# 19_PWR_VRS.net
KiCad netlist of a schematic drawn in Altium Designer
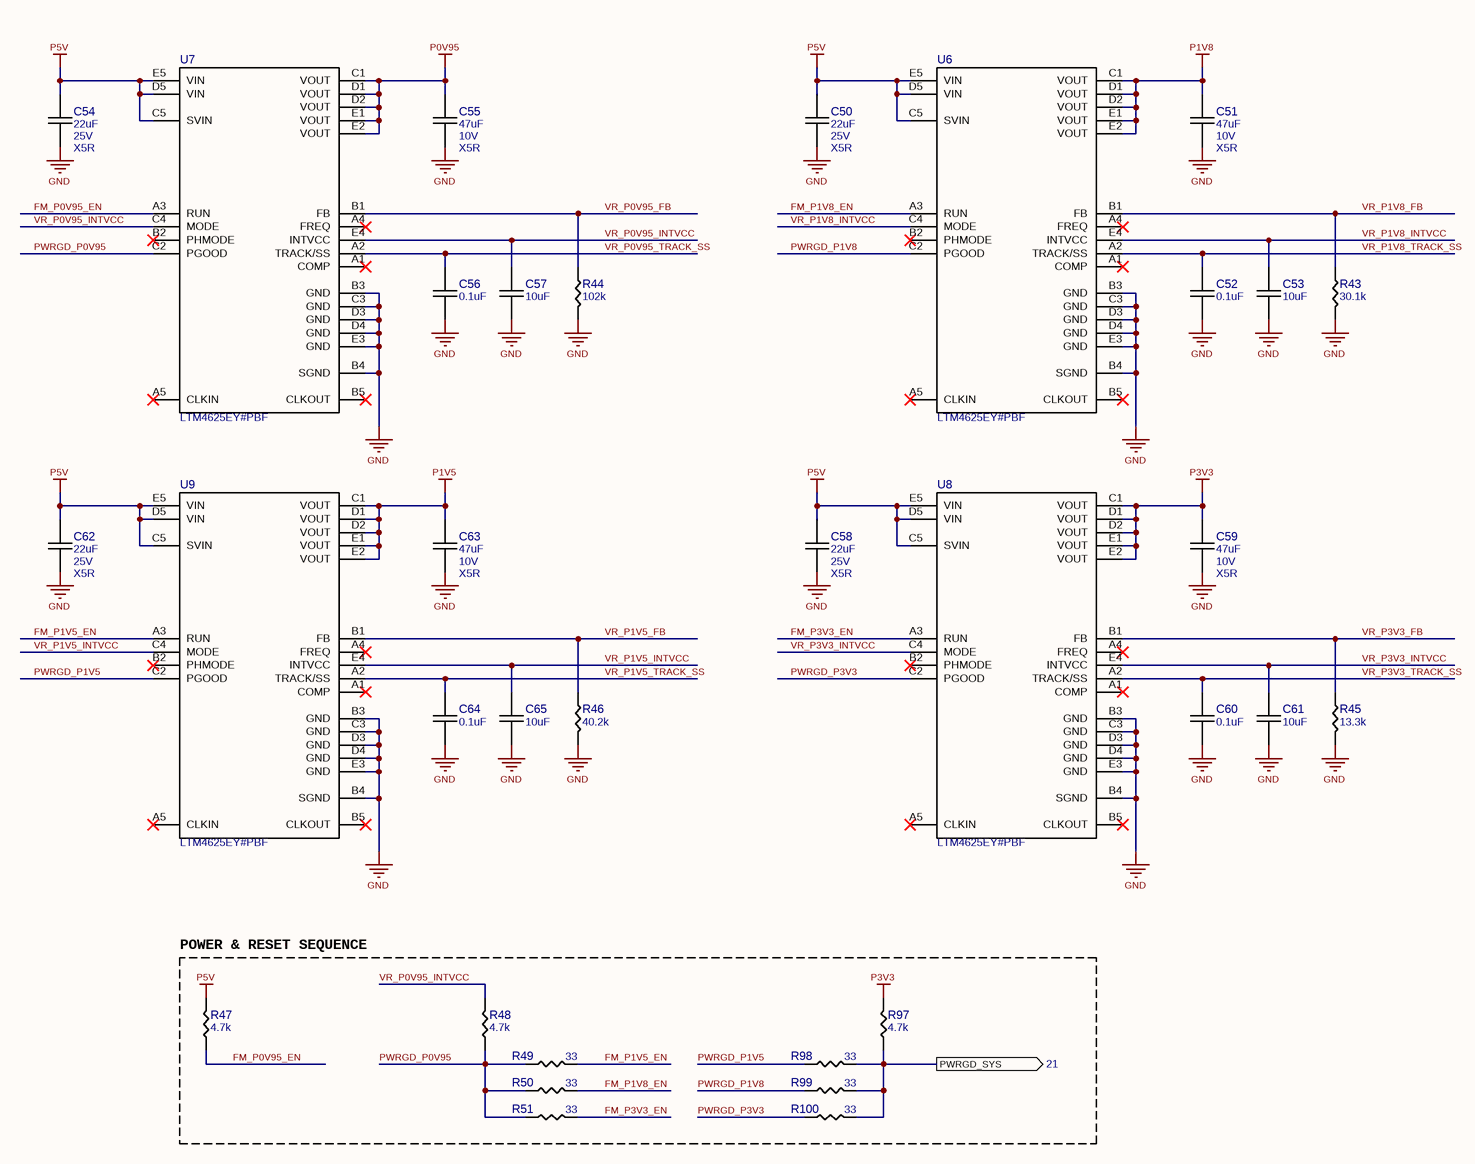
[diagram p0: 19_PWR_VRS.SchDoc]

(export (version "E")
  (design (tool "Eeschema 10.0.6"))
  (components
    (comp (ref "C50")
      (value "22uF")
      (footprint "CAPC2012X14N")
      (description "CAP CER 22UF 25V X5R 0805")
      (fields
        (field (name "PART NUMBER") "GRM21BR61E226ME44L")
        (field (name "VOLTAGE") "25V")
        (field (name "TEMPC") "X5R")
      )
      (libsource (lib "Database") (part "Capacitor"))
    )
    (comp (ref "C51")
      (value "47uF")
      (footprint "CAPC2012X14N")
      (description "CAP CER 47UF 10V X5R 0805")
      (fields
        (field (name "PART NUMBER") "GRM21BR61A476ME15L")
        (field (name "VOLTAGE") "10V")
        (field (name "TEMPC") "X5R")
      )
      (libsource (lib "Database") (part "Capacitor"))
    )
    (comp (ref "C52")
      (value "0.1uF")
      (footprint "CAPC1005X06N")
      (description "CAP CER 0.1UF 25V X7R 0402")
      (fields (field (name "PART NUMBER") "GRM155R71E104KE14J") (field (name "VOLTAGE") "25V"))
      (libsource (lib "Database") (part "Capacitor"))
    )
    (comp (ref "C53")
      (value "10uF")
      (footprint "CAPC1005X06N")
      (description "CAP CER 10UF 6.3V X5R 0402")
      (fields (field (name "PART NUMBER") "GRM155R60J106ME47D") (field (name "VOLTAGE") "6.3V"))
      (libsource (lib "Database") (part "Capacitor"))
    )
    (comp (ref "C54")
      (value "22uF")
      (footprint "CAPC2012X14N")
      (description "CAP CER 22UF 25V X5R 0805")
      (fields
        (field (name "PART NUMBER") "GRM21BR61E226ME44L")
        (field (name "VOLTAGE") "25V")
        (field (name "TEMPC") "X5R")
      )
      (libsource (lib "Database") (part "Capacitor"))
    )
    (comp (ref "C55")
      (value "47uF")
      (footprint "CAPC2012X14N")
      (description "CAP CER 47UF 10V X5R 0805")
      (fields
        (field (name "PART NUMBER") "GRM21BR61A476ME15L")
        (field (name "VOLTAGE") "10V")
        (field (name "TEMPC") "X5R")
      )
      (libsource (lib "Database") (part "Capacitor"))
    )
    (comp (ref "C56")
      (value "0.1uF")
      (footprint "CAPC1005X06N")
      (description "CAP CER 0.1UF 25V X7R 0402")
      (fields (field (name "PART NUMBER") "GRM155R71E104KE14J") (field (name "VOLTAGE") "25V"))
      (libsource (lib "Database") (part "Capacitor"))
    )
    (comp (ref "C57")
      (value "10uF")
      (footprint "CAPC1005X06N")
      (description "CAP CER 10UF 6.3V X5R 0402")
      (fields (field (name "PART NUMBER") "GRM155R60J106ME47D") (field (name "VOLTAGE") "6.3V"))
      (libsource (lib "Database") (part "Capacitor"))
    )
    (comp (ref "C58")
      (value "22uF")
      (footprint "CAPC2012X14N")
      (description "CAP CER 22UF 25V X5R 0805")
      (fields
        (field (name "PART NUMBER") "GRM21BR61E226ME44L")
        (field (name "VOLTAGE") "25V")
        (field (name "TEMPC") "X5R")
      )
      (libsource (lib "Database") (part "Capacitor"))
    )
    (comp (ref "C59")
      (value "47uF")
      (footprint "CAPC2012X14N")
      (description "CAP CER 47UF 10V X5R 0805")
      (fields
        (field (name "PART NUMBER") "GRM21BR61A476ME15L")
        (field (name "VOLTAGE") "10V")
        (field (name "TEMPC") "X5R")
      )
      (libsource (lib "Database") (part "Capacitor"))
    )
    (comp (ref "C60")
      (value "0.1uF")
      (footprint "CAPC1005X06N")
      (description "CAP CER 0.1UF 25V X7R 0402")
      (fields (field (name "PART NUMBER") "GRM155R71E104KE14J") (field (name "VOLTAGE") "25V"))
      (libsource (lib "Database") (part "Capacitor"))
    )
    (comp (ref "C61")
      (value "10uF")
      (footprint "CAPC1005X06N")
      (description "CAP CER 10UF 6.3V X5R 0402")
      (fields (field (name "PART NUMBER") "GRM155R60J106ME47D") (field (name "VOLTAGE") "6.3V"))
      (libsource (lib "Database") (part "Capacitor"))
    )
    (comp (ref "C62")
      (value "22uF")
      (footprint "CAPC2012X14N")
      (description "CAP CER 22UF 25V X5R 0805")
      (fields
        (field (name "PART NUMBER") "GRM21BR61E226ME44L")
        (field (name "VOLTAGE") "25V")
        (field (name "TEMPC") "X5R")
      )
      (libsource (lib "Database") (part "Capacitor"))
    )
    (comp (ref "C63")
      (value "47uF")
      (footprint "CAPC2012X14N")
      (description "CAP CER 47UF 10V X5R 0805")
      (fields
        (field (name "PART NUMBER") "GRM21BR61A476ME15L")
        (field (name "VOLTAGE") "10V")
        (field (name "TEMPC") "X5R")
      )
      (libsource (lib "Database") (part "Capacitor"))
    )
    (comp (ref "C64")
      (value "0.1uF")
      (footprint "CAPC1005X06N")
      (description "CAP CER 0.1UF 25V X7R 0402")
      (fields (field (name "PART NUMBER") "GRM155R71E104KE14J") (field (name "VOLTAGE") "25V"))
      (libsource (lib "Database") (part "Capacitor"))
    )
    (comp (ref "C65")
      (value "10uF")
      (footprint "CAPC1005X06N")
      (description "CAP CER 10UF 6.3V X5R 0402")
      (fields (field (name "PART NUMBER") "GRM155R60J106ME47D") (field (name "VOLTAGE") "6.3V"))
      (libsource (lib "Database") (part "Capacitor"))
    )
    (comp (ref "R43")
      (value "30.1k")
      (footprint "RESC1005X03N")
      (description "RES 30.1K OHM 1% 1/16W 0402")
      (fields (field (name "PART NUMBER") "RC0402FR-0730K1L"))
      (libsource (lib "Database") (part "Resistor_ENG"))
    )
    (comp (ref "R44")
      (value "102k")
      (footprint "RESC1005X03N")
      (description "RES SMD 102K OHM 1% 1/16W 0402")
      (fields (field (name "PART NUMBER") "RC0402FR-07102KL"))
      (libsource (lib "Database") (part "Resistor_ENG"))
    )
    (comp (ref "R45")
      (value "13.3k")
      (footprint "RESC1005X03N")
      (description "RES 13.3K OHM 1% 1/16W 0402")
      (fields (field (name "PART NUMBER") "RC0402FR-0713K3L"))
      (libsource (lib "Database") (part "Resistor_ENG"))
    )
    (comp (ref "R46")
      (value "40.2k")
      (footprint "RESC1005X03N")
      (description "RES 40.2K OHM 1% 1/16W 0402")
      (fields (field (name "PART NUMBER") "RC0402FR-0740K2L"))
      (libsource (lib "Database") (part "Resistor_ENG"))
    )
    (comp (ref "R47")
      (value "4.7k")
      (footprint "RESC1005X03N")
      (description "RES SMD 4.7K OHM 1% 1/16W 0402")
      (fields (field (name "PART NUMBER") "RC0402FR-074K7L"))
      (libsource (lib "Database") (part "Resistor_ENG"))
    )
    (comp (ref "R48")
      (value "4.7k")
      (footprint "RESC1005X03N")
      (description "RES SMD 4.7K OHM 1% 1/16W 0402")
      (fields (field (name "PART NUMBER") "RC0402FR-074K7L"))
      (libsource (lib "Database") (part "Resistor_ENG"))
    )
    (comp (ref "R49")
      (value "33")
      (footprint "RESC1005X03N")
      (description "RES SMD 33 OHM 1% 1/16W 0402")
      (fields (field (name "PART NUMBER") "RC0402FR-0733RL"))
      (libsource (lib "Database") (part "Resistor_ENG"))
    )
    (comp (ref "R50")
      (value "33")
      (footprint "RESC1005X03N")
      (description "RES SMD 33 OHM 1% 1/16W 0402")
      (fields (field (name "PART NUMBER") "RC0402FR-0733RL"))
      (libsource (lib "Database") (part "Resistor_ENG"))
    )
    (comp (ref "R51")
      (value "33")
      (footprint "RESC1005X03N")
      (description "RES SMD 33 OHM 1% 1/16W 0402")
      (fields (field (name "PART NUMBER") "RC0402FR-0733RL"))
      (libsource (lib "Database") (part "Resistor_ENG"))
    )
    (comp (ref "R97")
      (value "4.7k")
      (footprint "RESC1005X03N")
      (description "RES SMD 4.7K OHM 1% 1/16W 0402")
      (fields (field (name "PART NUMBER") "RC0402FR-074K7L"))
      (libsource (lib "Database") (part "Resistor_ENG"))
    )
    (comp (ref "R98")
      (value "33")
      (footprint "RESC1005X03N")
      (description "RES SMD 33 OHM 1% 1/16W 0402")
      (fields (field (name "PART NUMBER") "RC0402FR-0733RL"))
      (libsource (lib "Database") (part "Resistor_ENG"))
    )
    (comp (ref "R99")
      (value "33")
      (footprint "RESC1005X03N")
      (description "RES SMD 33 OHM 1% 1/16W 0402")
      (fields (field (name "PART NUMBER") "RC0402FR-0733RL"))
      (libsource (lib "Database") (part "Resistor_ENG"))
    )
    (comp (ref "R100")
      (value "33")
      (footprint "RESC1005X03N")
      (description "RES SMD 33 OHM 1% 1/16W 0402")
      (fields (field (name "PART NUMBER") "RC0402FR-0733RL"))
      (libsource (lib "Database") (part "Resistor_ENG"))
    )
    (comp (ref "U6")
      (value "LTM4625EY#PBF")
      (footprint "BGA25C127P5X5_625X625X521")
      (description "DC DC CONVERTER 0.6-5.5V")
      (libsource (lib "Database") (part "LTM4625"))
    )
    (comp (ref "U7")
      (value "LTM4625EY#PBF")
      (footprint "BGA25C127P5X5_625X625X521")
      (description "DC DC CONVERTER 0.6-5.5V")
      (libsource (lib "Database") (part "LTM4625"))
    )
    (comp (ref "U8")
      (value "LTM4625EY#PBF")
      (footprint "BGA25C127P5X5_625X625X521")
      (description "DC DC CONVERTER 0.6-5.5V")
      (libsource (lib "Database") (part "LTM4625"))
    )
    (comp (ref "U9")
      (value "LTM4625EY#PBF")
      (footprint "BGA25C127P5X5_625X625X521")
      (description "DC DC CONVERTER 0.6-5.5V")
      (libsource (lib "Database") (part "LTM4625"))
    )
  )
  (nets
    (net (code "1") (name "/FM_P0V95_EN") (class "Default")
      (node (ref "R47") (pin "1") (pinfunction "1_1") (pintype "passive"))
      (node (ref "U7") (pin "A3") (pinfunction "RUN_A3") (pintype "passive"))
    )
    (net (code "2") (name "/FM_P1V5_EN") (class "Default")
      (node (ref "R49") (pin "2") (pinfunction "2_2") (pintype "passive"))
      (node (ref "U9") (pin "A3") (pinfunction "RUN_A3") (pintype "passive"))
    )
    (net (code "3") (name "/FM_P1V8_EN") (class "Default")
      (node (ref "R50") (pin "2") (pinfunction "2_2") (pintype "passive"))
      (node (ref "U6") (pin "A3") (pinfunction "RUN_A3") (pintype "passive"))
    )
    (net (code "4") (name "/FM_P3V3_EN") (class "Default")
      (node (ref "R51") (pin "2") (pinfunction "2_2") (pintype "passive"))
      (node (ref "U8") (pin "A3") (pinfunction "RUN_A3") (pintype "passive"))
    )
    (net (code "5") (name "/PWRGD_P0V95") (class "Default")
      (node (ref "R48") (pin "1") (pinfunction "1_1") (pintype "passive"))
      (node (ref "R49") (pin "1") (pinfunction "1_1") (pintype "passive"))
      (node (ref "R50") (pin "1") (pinfunction "1_1") (pintype "passive"))
      (node (ref "R51") (pin "1") (pinfunction "1_1") (pintype "passive"))
      (node (ref "U7") (pin "C2") (pinfunction "PGOOD_C2") (pintype "passive"))
    )
    (net (code "6") (name "/PWRGD_P1V5") (class "Default")
      (node (ref "R98") (pin "1") (pinfunction "1_1") (pintype "passive"))
      (node (ref "U9") (pin "C2") (pinfunction "PGOOD_C2") (pintype "passive"))
    )
    (net (code "7") (name "/PWRGD_P1V8") (class "Default")
      (node (ref "R99") (pin "1") (pinfunction "1_1") (pintype "passive"))
      (node (ref "U6") (pin "C2") (pinfunction "PGOOD_C2") (pintype "passive"))
    )
    (net (code "8") (name "/PWRGD_P3V3") (class "Default")
      (node (ref "R100") (pin "1") (pinfunction "1_1") (pintype "passive"))
      (node (ref "U8") (pin "C2") (pinfunction "PGOOD_C2") (pintype "passive"))
    )
    (net (code "9") (name "/PWRGD_SYS") (class "Default")
      (node (ref "R100") (pin "2") (pinfunction "2_2") (pintype "passive"))
      (node (ref "R97") (pin "1") (pinfunction "1_1") (pintype "passive"))
      (node (ref "R98") (pin "2") (pinfunction "2_2") (pintype "passive"))
      (node (ref "R99") (pin "2") (pinfunction "2_2") (pintype "passive"))
    )
    (net (code "10") (name "/VR_P0V95_FB") (class "Default")
      (node (ref "R44") (pin "1") (pinfunction "1_1") (pintype "passive"))
      (node (ref "U7") (pin "B1") (pinfunction "FB_B1") (pintype "passive"))
    )
    (net (code "11") (name "/VR_P0V95_INTVCC") (class "Default")
      (node (ref "C57") (pin "2") (pinfunction "2_2") (pintype "passive"))
      (node (ref "R48") (pin "2") (pinfunction "2_2") (pintype "passive"))
      (node (ref "U7") (pin "C4") (pinfunction "MODE_C4") (pintype "passive"))
      (node (ref "U7") (pin "E4") (pinfunction "INTVCC_E4") (pintype "passive"))
    )
    (net (code "12") (name "/VR_P0V95_TRACK_SS") (class "Default")
      (node (ref "C56") (pin "2") (pinfunction "2_2") (pintype "passive"))
      (node (ref "U7") (pin "A2") (pinfunction "TRACK/SS_A2") (pintype "passive"))
    )
    (net (code "13") (name "/VR_P1V5_FB") (class "Default")
      (node (ref "R46") (pin "1") (pinfunction "1_1") (pintype "passive"))
      (node (ref "U9") (pin "B1") (pinfunction "FB_B1") (pintype "passive"))
    )
    (net (code "14") (name "/VR_P1V5_INTVCC") (class "Default")
      (node (ref "C65") (pin "2") (pinfunction "2_2") (pintype "passive"))
      (node (ref "U9") (pin "C4") (pinfunction "MODE_C4") (pintype "passive"))
      (node (ref "U9") (pin "E4") (pinfunction "INTVCC_E4") (pintype "passive"))
    )
    (net (code "15") (name "/VR_P1V5_TRACK_SS") (class "Default")
      (node (ref "C64") (pin "2") (pinfunction "2_2") (pintype "passive"))
      (node (ref "U9") (pin "A2") (pinfunction "TRACK/SS_A2") (pintype "passive"))
    )
    (net (code "16") (name "/VR_P1V8_FB") (class "Default")
      (node (ref "R43") (pin "1") (pinfunction "1_1") (pintype "passive"))
      (node (ref "U6") (pin "B1") (pinfunction "FB_B1") (pintype "passive"))
    )
    (net (code "17") (name "/VR_P1V8_INTVCC") (class "Default")
      (node (ref "C53") (pin "2") (pinfunction "2_2") (pintype "passive"))
      (node (ref "U6") (pin "C4") (pinfunction "MODE_C4") (pintype "passive"))
      (node (ref "U6") (pin "E4") (pinfunction "INTVCC_E4") (pintype "passive"))
    )
    (net (code "18") (name "/VR_P1V8_TRACK_SS") (class "Default")
      (node (ref "C52") (pin "2") (pinfunction "2_2") (pintype "passive"))
      (node (ref "U6") (pin "A2") (pinfunction "TRACK/SS_A2") (pintype "passive"))
    )
    (net (code "19") (name "/VR_P3V3_FB") (class "Default")
      (node (ref "R45") (pin "1") (pinfunction "1_1") (pintype "passive"))
      (node (ref "U8") (pin "B1") (pinfunction "FB_B1") (pintype "passive"))
    )
    (net (code "20") (name "/VR_P3V3_INTVCC") (class "Default")
      (node (ref "C61") (pin "2") (pinfunction "2_2") (pintype "passive"))
      (node (ref "U8") (pin "C4") (pinfunction "MODE_C4") (pintype "passive"))
      (node (ref "U8") (pin "E4") (pinfunction "INTVCC_E4") (pintype "passive"))
    )
    (net (code "21") (name "/VR_P3V3_TRACK_SS") (class "Default")
      (node (ref "C60") (pin "2") (pinfunction "2_2") (pintype "passive"))
      (node (ref "U8") (pin "A2") (pinfunction "TRACK/SS_A2") (pintype "passive"))
    )
    (net (code "22") (name "GND") (class "Default")
      (node (ref "C50") (pin "1") (pinfunction "1_1") (pintype "passive"))
      (node (ref "C51") (pin "1") (pinfunction "1_1") (pintype "passive"))
      (node (ref "C52") (pin "1") (pinfunction "1_1") (pintype "passive"))
      (node (ref "C53") (pin "1") (pinfunction "1_1") (pintype "passive"))
      (node (ref "C54") (pin "1") (pinfunction "1_1") (pintype "passive"))
      (node (ref "C55") (pin "1") (pinfunction "1_1") (pintype "passive"))
      (node (ref "C56") (pin "1") (pinfunction "1_1") (pintype "passive"))
      (node (ref "C57") (pin "1") (pinfunction "1_1") (pintype "passive"))
      (node (ref "C58") (pin "1") (pinfunction "1_1") (pintype "passive"))
      (node (ref "C59") (pin "1") (pinfunction "1_1") (pintype "passive"))
      (node (ref "C60") (pin "1") (pinfunction "1_1") (pintype "passive"))
      (node (ref "C61") (pin "1") (pinfunction "1_1") (pintype "passive"))
      (node (ref "C62") (pin "1") (pinfunction "1_1") (pintype "passive"))
      (node (ref "C63") (pin "1") (pinfunction "1_1") (pintype "passive"))
      (node (ref "C64") (pin "1") (pinfunction "1_1") (pintype "passive"))
      (node (ref "C65") (pin "1") (pinfunction "1_1") (pintype "passive"))
      (node (ref "R43") (pin "2") (pinfunction "2_2") (pintype "passive"))
      (node (ref "R44") (pin "2") (pinfunction "2_2") (pintype "passive"))
      (node (ref "R45") (pin "2") (pinfunction "2_2") (pintype "passive"))
      (node (ref "R46") (pin "2") (pinfunction "2_2") (pintype "passive"))
      (node (ref "U6") (pin "B3") (pinfunction "GND_B3") (pintype "passive"))
      (node (ref "U6") (pin "B4") (pinfunction "SGND_B4") (pintype "passive"))
      (node (ref "U6") (pin "C3") (pinfunction "GND_C3") (pintype "passive"))
      (node (ref "U6") (pin "D3") (pinfunction "GND_D3") (pintype "passive"))
      (node (ref "U6") (pin "D4") (pinfunction "GND_D4") (pintype "passive"))
      (node (ref "U6") (pin "E3") (pinfunction "GND_E3") (pintype "passive"))
      (node (ref "U7") (pin "B3") (pinfunction "GND_B3") (pintype "passive"))
      (node (ref "U7") (pin "B4") (pinfunction "SGND_B4") (pintype "passive"))
      (node (ref "U7") (pin "C3") (pinfunction "GND_C3") (pintype "passive"))
      (node (ref "U7") (pin "D3") (pinfunction "GND_D3") (pintype "passive"))
      (node (ref "U7") (pin "D4") (pinfunction "GND_D4") (pintype "passive"))
      (node (ref "U7") (pin "E3") (pinfunction "GND_E3") (pintype "passive"))
      (node (ref "U8") (pin "B3") (pinfunction "GND_B3") (pintype "passive"))
      (node (ref "U8") (pin "B4") (pinfunction "SGND_B4") (pintype "passive"))
      (node (ref "U8") (pin "C3") (pinfunction "GND_C3") (pintype "passive"))
      (node (ref "U8") (pin "D3") (pinfunction "GND_D3") (pintype "passive"))
      (node (ref "U8") (pin "D4") (pinfunction "GND_D4") (pintype "passive"))
      (node (ref "U8") (pin "E3") (pinfunction "GND_E3") (pintype "passive"))
      (node (ref "U9") (pin "B3") (pinfunction "GND_B3") (pintype "passive"))
      (node (ref "U9") (pin "B4") (pinfunction "SGND_B4") (pintype "passive"))
      (node (ref "U9") (pin "C3") (pinfunction "GND_C3") (pintype "passive"))
      (node (ref "U9") (pin "D3") (pinfunction "GND_D3") (pintype "passive"))
      (node (ref "U9") (pin "D4") (pinfunction "GND_D4") (pintype "passive"))
      (node (ref "U9") (pin "E3") (pinfunction "GND_E3") (pintype "passive"))
    )
    (net (code "23") (name "P0V95") (class "Default")
      (node (ref "C55") (pin "2") (pinfunction "2_2") (pintype "passive"))
      (node (ref "U7") (pin "C1") (pinfunction "VOUT_C1") (pintype "passive"))
      (node (ref "U7") (pin "D1") (pinfunction "VOUT_D1") (pintype "passive"))
      (node (ref "U7") (pin "D2") (pinfunction "VOUT_D2") (pintype "passive"))
      (node (ref "U7") (pin "E1") (pinfunction "VOUT_E1") (pintype "passive"))
      (node (ref "U7") (pin "E2") (pinfunction "VOUT_E2") (pintype "passive"))
    )
    (net (code "24") (name "P1V5") (class "Default")
      (node (ref "C63") (pin "2") (pinfunction "2_2") (pintype "passive"))
      (node (ref "U9") (pin "C1") (pinfunction "VOUT_C1") (pintype "passive"))
      (node (ref "U9") (pin "D1") (pinfunction "VOUT_D1") (pintype "passive"))
      (node (ref "U9") (pin "D2") (pinfunction "VOUT_D2") (pintype "passive"))
      (node (ref "U9") (pin "E1") (pinfunction "VOUT_E1") (pintype "passive"))
      (node (ref "U9") (pin "E2") (pinfunction "VOUT_E2") (pintype "passive"))
    )
    (net (code "25") (name "P1V8") (class "Default")
      (node (ref "C51") (pin "2") (pinfunction "2_2") (pintype "passive"))
      (node (ref "U6") (pin "C1") (pinfunction "VOUT_C1") (pintype "passive"))
      (node (ref "U6") (pin "D1") (pinfunction "VOUT_D1") (pintype "passive"))
      (node (ref "U6") (pin "D2") (pinfunction "VOUT_D2") (pintype "passive"))
      (node (ref "U6") (pin "E1") (pinfunction "VOUT_E1") (pintype "passive"))
      (node (ref "U6") (pin "E2") (pinfunction "VOUT_E2") (pintype "passive"))
    )
    (net (code "26") (name "P3V3") (class "Default")
      (node (ref "C59") (pin "2") (pinfunction "2_2") (pintype "passive"))
      (node (ref "R97") (pin "2") (pinfunction "2_2") (pintype "passive"))
      (node (ref "U8") (pin "C1") (pinfunction "VOUT_C1") (pintype "passive"))
      (node (ref "U8") (pin "D1") (pinfunction "VOUT_D1") (pintype "passive"))
      (node (ref "U8") (pin "D2") (pinfunction "VOUT_D2") (pintype "passive"))
      (node (ref "U8") (pin "E1") (pinfunction "VOUT_E1") (pintype "passive"))
      (node (ref "U8") (pin "E2") (pinfunction "VOUT_E2") (pintype "passive"))
    )
    (net (code "27") (name "P5V") (class "Default")
      (node (ref "C50") (pin "2") (pinfunction "2_2") (pintype "passive"))
      (node (ref "C54") (pin "2") (pinfunction "2_2") (pintype "passive"))
      (node (ref "C58") (pin "2") (pinfunction "2_2") (pintype "passive"))
      (node (ref "C62") (pin "2") (pinfunction "2_2") (pintype "passive"))
      (node (ref "R47") (pin "2") (pinfunction "2_2") (pintype "passive"))
      (node (ref "U6") (pin "C5") (pinfunction "SVIN_C5") (pintype "passive"))
      (node (ref "U6") (pin "D5") (pinfunction "VIN_D5") (pintype "passive"))
      (node (ref "U6") (pin "E5") (pinfunction "VIN_E5") (pintype "passive"))
      (node (ref "U7") (pin "C5") (pinfunction "SVIN_C5") (pintype "passive"))
      (node (ref "U7") (pin "D5") (pinfunction "VIN_D5") (pintype "passive"))
      (node (ref "U7") (pin "E5") (pinfunction "VIN_E5") (pintype "passive"))
      (node (ref "U8") (pin "C5") (pinfunction "SVIN_C5") (pintype "passive"))
      (node (ref "U8") (pin "D5") (pinfunction "VIN_D5") (pintype "passive"))
      (node (ref "U8") (pin "E5") (pinfunction "VIN_E5") (pintype "passive"))
      (node (ref "U9") (pin "C5") (pinfunction "SVIN_C5") (pintype "passive"))
      (node (ref "U9") (pin "D5") (pinfunction "VIN_D5") (pintype "passive"))
      (node (ref "U9") (pin "E5") (pinfunction "VIN_E5") (pintype "passive"))
    )
    (net (code "28") (name "unconnected-(U6-CLKIN-PadA5)") (class "Default")
      (node (ref "U6") (pin "A5") (pinfunction "CLKIN_A5") (pintype "passive+no_connect"))
    )
    (net (code "29") (name "unconnected-(U6-CLKOUT-PadB5)") (class "Default")
      (node (ref "U6") (pin "B5") (pinfunction "CLKOUT_B5") (pintype "passive+no_connect"))
    )
    (net (code "30") (name "unconnected-(U6-COMP-PadA1)") (class "Default")
      (node (ref "U6") (pin "A1") (pinfunction "COMP_A1") (pintype "passive+no_connect"))
    )
    (net (code "31") (name "unconnected-(U6-FREQ-PadA4)") (class "Default")
      (node (ref "U6") (pin "A4") (pinfunction "FREQ_A4") (pintype "passive+no_connect"))
    )
    (net (code "32") (name "unconnected-(U6-PHMODE-PadB2)") (class "Default")
      (node (ref "U6") (pin "B2") (pinfunction "PHMODE_B2") (pintype "passive+no_connect"))
    )
    (net (code "33") (name "unconnected-(U7-CLKIN-PadA5)") (class "Default")
      (node (ref "U7") (pin "A5") (pinfunction "CLKIN_A5") (pintype "passive+no_connect"))
    )
    (net (code "34") (name "unconnected-(U7-CLKOUT-PadB5)") (class "Default")
      (node (ref "U7") (pin "B5") (pinfunction "CLKOUT_B5") (pintype "passive+no_connect"))
    )
    (net (code "35") (name "unconnected-(U7-COMP-PadA1)") (class "Default")
      (node (ref "U7") (pin "A1") (pinfunction "COMP_A1") (pintype "passive+no_connect"))
    )
    (net (code "36") (name "unconnected-(U7-FREQ-PadA4)") (class "Default")
      (node (ref "U7") (pin "A4") (pinfunction "FREQ_A4") (pintype "passive+no_connect"))
    )
    (net (code "37") (name "unconnected-(U7-PHMODE-PadB2)") (class "Default")
      (node (ref "U7") (pin "B2") (pinfunction "PHMODE_B2") (pintype "passive+no_connect"))
    )
    (net (code "38") (name "unconnected-(U8-CLKIN-PadA5)") (class "Default")
      (node (ref "U8") (pin "A5") (pinfunction "CLKIN_A5") (pintype "passive+no_connect"))
    )
    (net (code "39") (name "unconnected-(U8-CLKOUT-PadB5)") (class "Default")
      (node (ref "U8") (pin "B5") (pinfunction "CLKOUT_B5") (pintype "passive+no_connect"))
    )
    (net (code "40") (name "unconnected-(U8-COMP-PadA1)") (class "Default")
      (node (ref "U8") (pin "A1") (pinfunction "COMP_A1") (pintype "passive+no_connect"))
    )
    (net (code "41") (name "unconnected-(U8-FREQ-PadA4)") (class "Default")
      (node (ref "U8") (pin "A4") (pinfunction "FREQ_A4") (pintype "passive+no_connect"))
    )
    (net (code "42") (name "unconnected-(U8-PHMODE-PadB2)") (class "Default")
      (node (ref "U8") (pin "B2") (pinfunction "PHMODE_B2") (pintype "passive+no_connect"))
    )
    (net (code "43") (name "unconnected-(U9-CLKIN-PadA5)") (class "Default")
      (node (ref "U9") (pin "A5") (pinfunction "CLKIN_A5") (pintype "passive+no_connect"))
    )
    (net (code "44") (name "unconnected-(U9-CLKOUT-PadB5)") (class "Default")
      (node (ref "U9") (pin "B5") (pinfunction "CLKOUT_B5") (pintype "passive+no_connect"))
    )
    (net (code "45") (name "unconnected-(U9-COMP-PadA1)") (class "Default")
      (node (ref "U9") (pin "A1") (pinfunction "COMP_A1") (pintype "passive+no_connect"))
    )
    (net (code "46") (name "unconnected-(U9-FREQ-PadA4)") (class "Default")
      (node (ref "U9") (pin "A4") (pinfunction "FREQ_A4") (pintype "passive+no_connect"))
    )
    (net (code "47") (name "unconnected-(U9-PHMODE-PadB2)") (class "Default")
      (node (ref "U9") (pin "B2") (pinfunction "PHMODE_B2") (pintype "passive+no_connect"))
    )
  )
)
